# PIR_D205.net
KiCad netlist of a schematic drawn in EAGLE
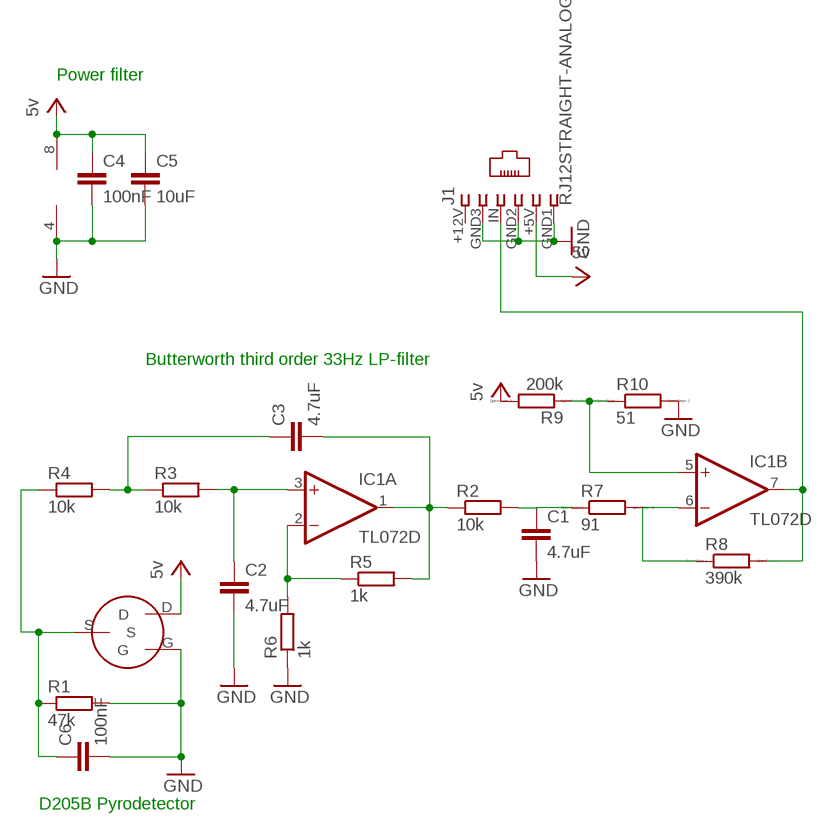
[diagram p0: schematic, sheet 1]

(export (version "E")
  (design (tool "Eeschema 10.0.6"))
  (components
    (comp (ref "C1")
      (value "4.7uF")
      (footprint "eagle-import:C1206")
      (libsource (lib "eagle-import") (part "C-EUC1206"))
    )
    (comp (ref "C2")
      (value "4.7uF")
      (footprint "eagle-import:C1206")
      (libsource (lib "eagle-import") (part "C-EUC1206"))
    )
    (comp (ref "C3")
      (value "4.7uF")
      (footprint "eagle-import:C1206")
      (libsource (lib "eagle-import") (part "C-EUC1206"))
    )
    (comp (ref "C4")
      (value "100nF")
      (footprint "eagle-import:C1206")
      (libsource (lib "eagle-import") (part "C-EUC1206"))
    )
    (comp (ref "C5")
      (value "10uF")
      (footprint "eagle-import:C1206")
      (libsource (lib "eagle-import") (part "C-EUC1206"))
    )
    (comp (ref "C6")
      (value "100nF")
      (footprint "eagle-import:C1206")
      (libsource (lib "eagle-import") (part "C-EUC1206"))
    )
    (comp (ref "IC1")
      (value "TL072D")
      (footprint "eagle-import:SO08")
      (libsource (lib "eagle-import") (part "TL072D"))
    )
    (comp (ref "J1")
      (value "RJ12STRAIGHT-ANALOG")
      (footprint "eagle-import:RJ12-STRAIGHT-ANALOG")
      (libsource (lib "eagle-import") (part "RJ12STRAIGHT-ANALOG"))
    )
    (comp (ref "R1")
      (value "47k")
      (footprint "eagle-import:R1206")
      (libsource (lib "eagle-import") (part "R-EU_R1206"))
    )
    (comp (ref "R2")
      (value "10k")
      (footprint "eagle-import:R0805")
      (libsource (lib "eagle-import") (part "R-EU_R0805"))
    )
    (comp (ref "R3")
      (value "10k")
      (footprint "eagle-import:R0805")
      (libsource (lib "eagle-import") (part "R-EU_R0805"))
    )
    (comp (ref "R4")
      (value "10k")
      (footprint "eagle-import:R0805")
      (libsource (lib "eagle-import") (part "R-EU_R0805"))
    )
    (comp (ref "R5")
      (value "1k")
      (footprint "eagle-import:R0805")
      (libsource (lib "eagle-import") (part "R-EU_R0805"))
    )
    (comp (ref "R6")
      (value "1k")
      (footprint "eagle-import:R0805")
      (libsource (lib "eagle-import") (part "R-EU_R0805"))
    )
    (comp (ref "R7")
      (value "91")
      (footprint "eagle-import:R1206")
      (libsource (lib "eagle-import") (part "resistor_R-EU_R1206"))
    )
    (comp (ref "R8")
      (value "390k")
      (footprint "eagle-import:R1206")
      (libsource (lib "eagle-import") (part "resistor_R-EU_R1206"))
    )
    (comp (ref "R9")
      (value "200k")
      (footprint "eagle-import:R1206")
      (libsource (lib "eagle-import") (part "resistor_R-EU_R1206"))
    )
    (comp (ref "R10")
      (value "51")
      (footprint "eagle-import:R1206")
      (libsource (lib "eagle-import") (part "resistor_R-EU_R1206"))
    )
    (comp (ref "U$1")
      (value "D205B")
      (footprint "eagle-import:TO5")
      (libsource (lib "eagle-import") (part "D205B"))
    )
  )
  (nets
    (net (code "1") (name "5v") (class "Default")
      (node (ref "C4") (pin "1") (pinfunction "1_1") (pintype "passive"))
      (node (ref "C5") (pin "1") (pinfunction "1_1") (pintype "passive"))
      (node (ref "IC1") (pin "8") (pinfunction "V+_8") (pintype "power_in"))
      (node (ref "J1") (pin "+5V") (pinfunction "5_+5V") (pintype "bidirectional"))
      (node (ref "R9") (pin "2") (pinfunction "2_2") (pintype "passive"))
      (node (ref "U$1") (pin "D") (pinfunction "D_D") (pintype "bidirectional"))
    )
    (net (code "2") (name "GND") (class "Default")
      (node (ref "C1") (pin "2") (pinfunction "2_2") (pintype "passive"))
      (node (ref "C2") (pin "2") (pinfunction "2_2") (pintype "passive"))
      (node (ref "C4") (pin "2") (pinfunction "2_2") (pintype "passive"))
      (node (ref "C5") (pin "2") (pinfunction "2_2") (pintype "passive"))
      (node (ref "C6") (pin "2") (pinfunction "2_2") (pintype "passive"))
      (node (ref "IC1") (pin "4") (pinfunction "V-_4") (pintype "power_in"))
      (node (ref "J1") (pin "GND1") (pinfunction "6_GND1") (pintype "bidirectional"))
      (node (ref "J1") (pin "GND2") (pinfunction "4_GND2") (pintype "bidirectional"))
      (node (ref "J1") (pin "GND3") (pinfunction "2_GND3") (pintype "bidirectional"))
      (node (ref "R1") (pin "2") (pinfunction "2_2") (pintype "passive"))
      (node (ref "R10") (pin "2") (pinfunction "2_2") (pintype "passive"))
      (node (ref "R6") (pin "1") (pinfunction "1_1") (pintype "passive"))
      (node (ref "U$1") (pin "G") (pinfunction "G_G") (pintype "bidirectional"))
    )
    (net (code "3") (name "Net-(C1-Pad1)") (class "Default")
      (node (ref "C1") (pin "1") (pinfunction "1_1") (pintype "passive"))
      (node (ref "R2") (pin "2") (pinfunction "2_2") (pintype "passive"))
      (node (ref "R7") (pin "1") (pinfunction "1_1") (pintype "passive"))
    )
    (net (code "4") (name "Net-(C3-Pad1)") (class "Default")
      (node (ref "C3") (pin "1") (pinfunction "1_1") (pintype "passive"))
      (node (ref "R3") (pin "1") (pinfunction "1_1") (pintype "passive"))
      (node (ref "R4") (pin "2") (pinfunction "2_2") (pintype "passive"))
    )
    (net (code "5") (name "Net-(C6-Pad1)") (class "Default")
      (node (ref "C6") (pin "1") (pinfunction "1_1") (pintype "passive"))
      (node (ref "R1") (pin "1") (pinfunction "1_1") (pintype "passive"))
      (node (ref "R4") (pin "1") (pinfunction "1_1") (pintype "passive"))
      (node (ref "U$1") (pin "S") (pinfunction "S_S") (pintype "bidirectional"))
    )
    (net (code "6") (name "Net-(IC1A-+IN)") (class "Default")
      (node (ref "C2") (pin "1") (pinfunction "1_1") (pintype "passive"))
      (node (ref "IC1") (pin "3") (pinfunction "+IN_3") (pintype "input"))
      (node (ref "R3") (pin "2") (pinfunction "2_2") (pintype "passive"))
    )
    (net (code "7") (name "Net-(IC1A--IN)") (class "Default")
      (node (ref "IC1") (pin "2") (pinfunction "-IN_2") (pintype "input"))
      (node (ref "R5") (pin "1") (pinfunction "1_1") (pintype "passive"))
      (node (ref "R6") (pin "2") (pinfunction "2_2") (pintype "passive"))
    )
    (net (code "8") (name "Net-(IC1A-OUT)") (class "Default")
      (node (ref "C3") (pin "2") (pinfunction "2_2") (pintype "passive"))
      (node (ref "IC1") (pin "1") (pinfunction "OUT_1") (pintype "output"))
      (node (ref "R2") (pin "1") (pinfunction "1_1") (pintype "passive"))
      (node (ref "R5") (pin "2") (pinfunction "2_2") (pintype "passive"))
    )
    (net (code "9") (name "Net-(IC1B-+IN)") (class "Default")
      (node (ref "IC1") (pin "5") (pinfunction "+IN_5") (pintype "input"))
      (node (ref "R10") (pin "1") (pinfunction "1_1") (pintype "passive"))
      (node (ref "R9") (pin "1") (pinfunction "1_1") (pintype "passive"))
    )
    (net (code "10") (name "Net-(IC1B--IN)") (class "Default")
      (node (ref "IC1") (pin "6") (pinfunction "-IN_6") (pintype "input"))
      (node (ref "R7") (pin "2") (pinfunction "2_2") (pintype "passive"))
      (node (ref "R8") (pin "1") (pinfunction "1_1") (pintype "passive"))
    )
    (net (code "11") (name "Net-(IC1B-OUT)") (class "Default")
      (node (ref "IC1") (pin "7") (pinfunction "OUT_7") (pintype "output"))
      (node (ref "J1") (pin "IN") (pinfunction "3_IN") (pintype "bidirectional"))
      (node (ref "R8") (pin "2") (pinfunction "2_2") (pintype "passive"))
    )
    (net (code "12") (name "unconnected-(J1-1-Pad+12V)") (class "Default")
      (node (ref "J1") (pin "+12V") (pinfunction "1_+12V") (pintype "bidirectional"))
    )
  )
)
